# Microcontroller.net
KiCad netlist of a schematic drawn in Altium Designer
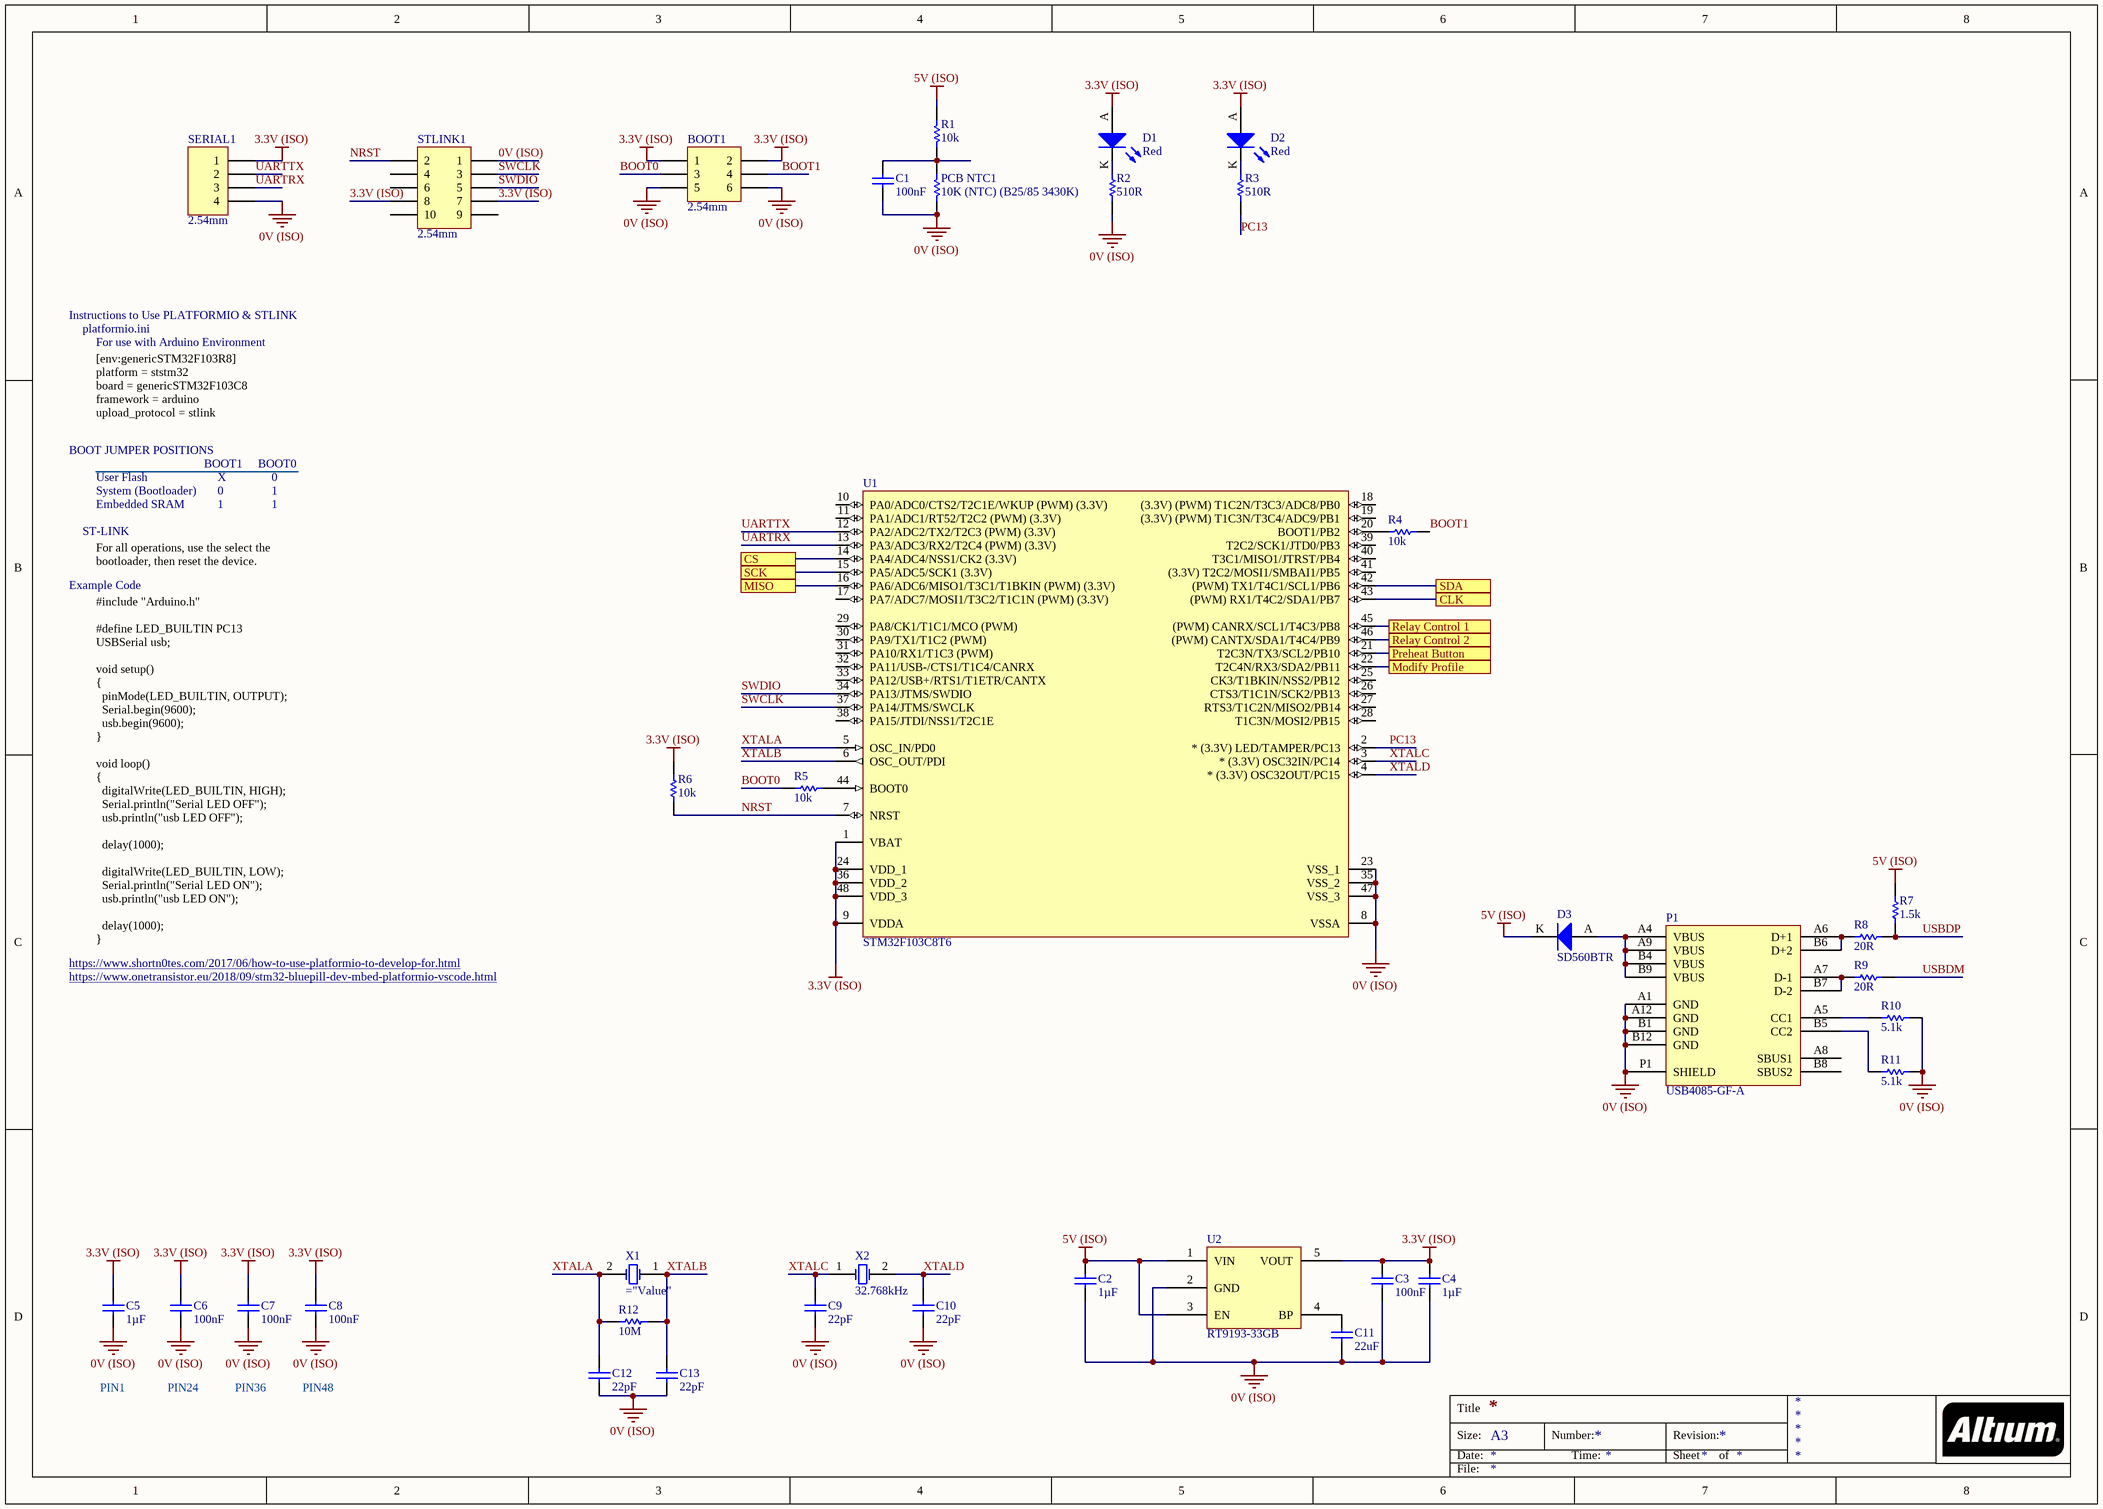
[diagram p0: Microcontroller.SchDoc]

(export (version "E")
  (design (tool "Eeschema 10.0.6"))
  (components
    (comp (ref "BOOT1")
      (value "2.54mm")
      (footprint "TH 2.54mm Header 2x3")
      (fields (field (name "PART NUMBER") "TH 2.54mm Header 2x3") (field (name "CONTACT") "NA"))
      (libsource (lib "ts_20-standard-connectors") (part "Header 2x3"))
    )
    (comp (ref "C1")
      (value "100nF")
      (footprint "0805")
      (fields
        (field (name "PART NUMBER") "GCM21BR71E104KA37L")
        (field (name "TOLERANCE") "10%")
        (field (name "MANUFACTURER") "muRata")
      )
      (libsource (lib "ts_20-standard-library") (part "Capacitor"))
    )
    (comp (ref "C2")
      (value "1µF")
      (footprint "0805")
      (fields
        (field (name "PART NUMBER") "GCM21BR71H105KA03L")
        (field (name "TOLERANCE") "±10%")
        (field (name "MANUFACTURER") "muRata")
      )
      (libsource (lib "ts_20-standard-library") (part "Capacitor"))
    )
    (comp (ref "C3")
      (value "100nF")
      (footprint "0805")
      (fields
        (field (name "PART NUMBER") "GCM21BR71H104KA37L")
        (field (name "TOLERANCE") "±10%")
        (field (name "MANUFACTURER") "muRata")
      )
      (libsource (lib "ts_20-standard-library") (part "Capacitor"))
    )
    (comp (ref "C4")
      (value "1µF")
      (footprint "0805")
      (fields
        (field (name "PART NUMBER") "GCM21BR71H105KA03L")
        (field (name "TOLERANCE") "±10%")
        (field (name "MANUFACTURER") "muRata")
      )
      (libsource (lib "ts_20-standard-library") (part "Capacitor"))
    )
    (comp (ref "C5")
      (value "1µF")
      (footprint "0805")
      (fields
        (field (name "PART NUMBER") "GCM21BR71H105KA03L")
        (field (name "TOLERANCE") "±10%")
        (field (name "MANUFACTURER") "muRata")
      )
      (libsource (lib "ts_20-standard-library") (part "Capacitor"))
    )
    (comp (ref "C6")
      (value "100nF")
      (footprint "0805")
      (fields
        (field (name "PART NUMBER") "GCM21BR71H104KA37L")
        (field (name "TOLERANCE") "±10%")
        (field (name "MANUFACTURER") "muRata")
      )
      (libsource (lib "ts_20-standard-library") (part "Capacitor"))
    )
    (comp (ref "C7")
      (value "100nF")
      (footprint "0805")
      (fields
        (field (name "PART NUMBER") "GCM21BR71H104KA37L")
        (field (name "TOLERANCE") "±10%")
        (field (name "MANUFACTURER") "muRata")
      )
      (libsource (lib "ts_20-standard-library") (part "Capacitor"))
    )
    (comp (ref "C8")
      (value "100nF")
      (footprint "0805")
      (fields
        (field (name "PART NUMBER") "GCM21BR71H104KA37L")
        (field (name "TOLERANCE") "±10%")
        (field (name "MANUFACTURER") "muRata")
      )
      (libsource (lib "ts_20-standard-library") (part "Capacitor"))
    )
    (comp (ref "C9")
      (value "22pF")
      (footprint "0805")
      (fields
        (field (name "PART NUMBER") "GRM21A5C2E220JW01D")
        (field (name "TOLERANCE") "±5%")
        (field (name "MANUFACTURER") "muRata")
      )
      (libsource (lib "ts_20-standard-library") (part "Capacitor"))
    )
    (comp (ref "C10")
      (value "22pF")
      (footprint "0805")
      (fields
        (field (name "PART NUMBER") "GRM21A5C2E220JW01D")
        (field (name "TOLERANCE") "±5%")
        (field (name "MANUFACTURER") "muRata")
      )
      (libsource (lib "ts_20-standard-library") (part "Capacitor"))
    )
    (comp (ref "C11")
      (value "22uF")
      (footprint "0805")
      (fields
        (field (name "PART NUMBER") "GRM21BR61A226ME51L")
        (field (name "TOLERANCE") "20%")
        (field (name "MANUFACTURER") "muRata")
      )
      (libsource (lib "ts_20-standard-library") (part "Capacitor"))
    )
    (comp (ref "C12")
      (value "22pF")
      (footprint "0805")
      (fields
        (field (name "PART NUMBER") "GRM21A5C2E220JW01D")
        (field (name "TOLERANCE") "±5%")
        (field (name "MANUFACTURER") "muRata")
      )
      (libsource (lib "ts_20-standard-library") (part "Capacitor"))
    )
    (comp (ref "C13")
      (value "22pF")
      (footprint "0805")
      (fields
        (field (name "PART NUMBER") "GRM21A5C2E220JW01D")
        (field (name "TOLERANCE") "±5%")
        (field (name "MANUFACTURER") "muRata")
      )
      (libsource (lib "ts_20-standard-library") (part "Capacitor"))
    )
    (comp (ref "D1")
      (value "Red")
      (footprint "0805 LED")
      (description "Red LED Indication - Discrete 1.75V 0805 (2012 Metric)")
      (fields (field (name "MANUFACTURER") "ROHM Semiconductor") (field (name "PART NUMBER") "SML-210LTT86"))
      (libsource (lib "ts_20-standard-library") (part "LED"))
    )
    (comp (ref "D2")
      (value "Red")
      (footprint "0805 LED")
      (description "Red LED Indication - Discrete 1.75V 0805 (2012 Metric)")
      (fields (field (name "MANUFACTURER") "ROHM Semiconductor") (field (name "PART NUMBER") "SML-210LTT86"))
      (libsource (lib "ts_20-standard-library") (part "LED"))
    )
    (comp (ref "D3")
      (value "SD560BTR")
      (footprint "SMB Diode")
      (description "1.2V_F 600V 5A SMB")
      (fields
        (field (name "MANUFACTURER") "SMC Diode Solutions")
        (field (name "DIGIKEY PART NUMBER") "1655-1530-2-ND")
      )
      (libsource (lib "ts_20-standard-library") (part "Diode"))
    )
    (comp (ref "P1")
      (value "USB4085-GF-A")
      (footprint "USB4085-GF-A")
      (description "USB - C (Type - C) USB 2.0 Receptacle Connector 16 Position Through Hole, Right Angle")
      (fields (field (name "DIGIKEY PART NUMBER") "2073-USB4085-GF-ACT-ND"))
      (libsource (lib "ts_20-standard-connectors") (part "USB4085-GF-A"))
    )
    (comp (ref "PCB NTC1")
      (value "10K (NTC) (B25/85 3430K)")
      (footprint "0805")
      (fields
        (field (name "PART NUMBER") "NTCS0805E3103FLT")
        (field (name "MANUFACTURER") "Vishay Beyschlag")
        (field (name "TOLERANCE") "0.01")
      )
      (libsource (lib "ts_20-standard-library") (part "Resistor"))
    )
    (comp (ref "R1")
      (value "10k")
      (footprint "0805")
      (fields
        (field (name "PART NUMBER") "RC0805FR0710KL")
        (field (name "MANUFACTURER") "YAGEO")
        (field (name "TOLERANCE") "0.01")
      )
      (libsource (lib "ts_20-standard-library") (part "Resistor"))
    )
    (comp (ref "R2")
      (value "510R")
      (footprint "0805")
      (fields
        (field (name "MANUFACTURER") "YAGEO")
        (field (name "PART NUMBER") "RC0805FR07510RL")
        (field (name "TOLERANCE") "0.01")
      )
      (libsource (lib "ts_20-standard-library") (part "Resistor"))
    )
    (comp (ref "R3")
      (value "510R")
      (footprint "0805")
      (fields
        (field (name "MANUFACTURER") "YAGEO")
        (field (name "PART NUMBER") "RC0805FR07510RL")
        (field (name "TOLERANCE") "0.01")
      )
      (libsource (lib "ts_20-standard-library") (part "Resistor"))
    )
    (comp (ref "R4")
      (value "10k")
      (footprint "0805")
      (fields
        (field (name "PART NUMBER") "RC0805FR0710KL")
        (field (name "MANUFACTURER") "YAGEO")
        (field (name "TOLERANCE") "0.01")
      )
      (libsource (lib "ts_20-standard-library") (part "Resistor"))
    )
    (comp (ref "R5")
      (value "10k")
      (footprint "0805")
      (fields
        (field (name "PART NUMBER") "RC0805FR0710KL")
        (field (name "MANUFACTURER") "YAGEO")
        (field (name "TOLERANCE") "0.01")
      )
      (libsource (lib "ts_20-standard-library") (part "Resistor"))
    )
    (comp (ref "R6")
      (value "10k")
      (footprint "0805")
      (fields
        (field (name "MANUFACTURER") "YAGEO")
        (field (name "PART NUMBER") "RC0805FR0710KL")
        (field (name "TOLERANCE") "0.01")
      )
      (libsource (lib "ts_20-standard-library") (part "Resistor"))
    )
    (comp (ref "R7")
      (value "1.5k")
      (footprint "0805")
      (fields
        (field (name "PART NUMBER") "RC0805FR071K5L")
        (field (name "MANUFACTURER") "YAGEO")
        (field (name "TOLERANCE") "0.01")
      )
      (libsource (lib "ts_20-standard-library") (part "Resistor"))
    )
    (comp (ref "R8")
      (value "20R")
      (footprint "0805")
      (fields
        (field (name "PART NUMBER") "RC0805FR0720RL")
        (field (name "MANUFACTURER") "YAGEO")
        (field (name "TOLERANCE") "0.01")
      )
      (libsource (lib "ts_20-standard-library") (part "Resistor"))
    )
    (comp (ref "R9")
      (value "20R")
      (footprint "0805")
      (fields
        (field (name "PART NUMBER") "RC0805FR0720RL")
        (field (name "MANUFACTURER") "YAGEO")
        (field (name "TOLERANCE") "0.01")
      )
      (libsource (lib "ts_20-standard-library") (part "Resistor"))
    )
    (comp (ref "R10")
      (value "5.1k")
      (footprint "0805")
      (fields
        (field (name "PART NUMBER") "RC0805FR075K1L")
        (field (name "MANUFACTURER") "YAGEO")
        (field (name "TOLERANCE") "0.01")
      )
      (libsource (lib "ts_20-standard-library") (part "Resistor"))
    )
    (comp (ref "R11")
      (value "5.1k")
      (footprint "0805")
      (fields
        (field (name "PART NUMBER") "RC0805FR075K1L")
        (field (name "MANUFACTURER") "YAGEO")
        (field (name "TOLERANCE") "0.01")
      )
      (libsource (lib "ts_20-standard-library") (part "Resistor"))
    )
    (comp (ref "R12")
      (value "10M")
      (footprint "0805")
      (fields
        (field (name "PART NUMBER") "RC0805FR0710ML")
        (field (name "MANUFACTURER") "YAGEO")
        (field (name "TOLERANCE") "0.01")
      )
      (libsource (lib "ts_20-standard-library") (part "Resistor"))
    )
    (comp (ref "SERIAL1")
      (value "2.54mm")
      (footprint "TH 2.54mm Header 1x4")
      (fields (field (name "PART NUMBER") "TH 2.54mm Header 1x4") (field (name "CONTACT") "NA"))
      (libsource (lib "ts_20-standard-connectors") (part "Header 1x4"))
    )
    (comp (ref "STLINK1")
      (value "2.54mm")
      (footprint "TH 2.54mm Header 2x5")
      (fields (field (name "PART NUMBER") "TH 2.54mm Header 2x5") (field (name "CONTACT") "NA"))
      (libsource (lib "ts_20-standard-connectors") (part "Header 2x5"))
    )
    (comp (ref "U1")
      (value "STM32F103C8T6")
      (footprint "STM 48-LQFP")
      (description "ARM® Cortex®-M3 STM32F1 Microcontroller IC 32-Bit 72MHz 64KB (64K x 8) FLASH")
      (fields
        (field (name "MANUFACTURER") "STMicroelectronics")
        (field (name "DIGIKEY PART NUMBER") "497-6063-ND")
      )
      (libsource (lib "ts_20-standard-library") (part "STM32F103C8T6"))
    )
    (comp (ref "U2")
      (value "RT9193-33GB")
      (footprint "RICHTEK SOT-23-5")
      (description "IC REG LINEAR 3.3V 300MA SOT23-5")
      (fields (field (name "MANUFACTURER") "Richtek") (field (name "DIGIKEY PART NUMBER") "1028-1014-1-ND"))
      (libsource (lib "ts_20-standard-library") (part "RT9193-33GB"))
    )
    (comp (ref "X1")
      (value "~")
      (footprint "Abracon HC-49/US")
      (fields
        (field (name "PART NUMBER") "ABLS-16.000MHZ-B4-T")
        (field (name "MANUFACTURER") "Abracon LLC")
        (field (name "DIGIKEY PART NUMBER") "535-10226-1-ND")
      )
      (libsource (lib "ts_20-standard-library") (part "Crystal"))
    )
    (comp (ref "X2")
      (value "32.768kHz")
      (footprint "EPSON 2-SMD")
      (fields
        (field (name "PART NUMBER") "FC-135 32.7680KA-A5")
        (field (name "MANUFACTURER") "EPSON")
        (field (name "DIGIKEY PART NUMBER") "SER4103TR-ND")
      )
      (libsource (lib "ts_20-standard-library") (part "Crystal"))
    )
  )
  (nets
    (net (code "1") (name "/BOOT0") (class "Default")
      (node (ref "BOOT1") (pin "3") (pinfunction "3_3") (pintype "passive"))
      (node (ref "R5") (pin "1") (pinfunction "1_1") (pintype "passive"))
    )
    (net (code "2") (name "/BOOT1") (class "Default")
      (node (ref "BOOT1") (pin "4") (pinfunction "4_4") (pintype "passive"))
      (node (ref "R4") (pin "2") (pinfunction "2_2") (pintype "passive"))
    )
    (net (code "3") (name "/CLK") (class "Default")
      (node (ref "U1") (pin "43") (pinfunction "(PWM)_RX1/T4C2/SDA1/PB7_43") (pintype "bidirectional"))
    )
    (net (code "4") (name "/CS") (class "Default")
      (node (ref "U1") (pin "14") (pinfunction "PA4/ADC4/NSS1/CK2_(3.3V)_14") (pintype "bidirectional"))
    )
    (net (code "5") (name "/MISO") (class "Default")
      (node (ref "U1") (pin "16") (pinfunction "PA6/ADC6/MISO1/T3C1/T1BKIN_(PWM)_(3.3V)_16") (pintype "bidirectional"))
    )
    (net (code "6") (name "/Modify Profile") (class "Default")
      (node (ref "U1") (pin "22") (pinfunction "T2C4N/RX3/SDA2/PB11_22") (pintype "bidirectional"))
    )
    (net (code "7") (name "/NRST") (class "Default")
      (node (ref "R6") (pin "1") (pinfunction "1_1") (pintype "passive"))
      (node (ref "STLINK1") (pin "2") (pinfunction "2_2") (pintype "passive"))
      (node (ref "U1") (pin "7") (pinfunction "NRST_7") (pintype "bidirectional"))
    )
    (net (code "8") (name "/PC13") (class "Default")
      (node (ref "R3") (pin "1") (pinfunction "1_1") (pintype "passive"))
      (node (ref "U1") (pin "2") (pinfunction "*_(3.3V)_LED/TAMPER/PC13_2") (pintype "bidirectional"))
    )
    (net (code "9") (name "/Preheat Button") (class "Default")
      (node (ref "U1") (pin "21") (pinfunction "T2C3N/TX3/SCL2/PB10_21") (pintype "bidirectional"))
    )
    (net (code "10") (name "/Relay Control 1") (class "Default")
      (node (ref "U1") (pin "45") (pinfunction "(PWM)_CANRX/SCL1/T4C3/PB8_45") (pintype "bidirectional"))
    )
    (net (code "11") (name "/Relay Control 2") (class "Default")
      (node (ref "U1") (pin "46") (pinfunction "(PWM)_CANTX/SDA1/T4C4/PB9_46") (pintype "bidirectional"))
    )
    (net (code "12") (name "/SCK") (class "Default")
      (node (ref "U1") (pin "15") (pinfunction "PA5/ADC5/SCK1_(3.3V)_15") (pintype "bidirectional"))
    )
    (net (code "13") (name "/SDA") (class "Default")
      (node (ref "U1") (pin "42") (pinfunction "(PWM)_TX1/T4C1/SCL1/PB6_42") (pintype "bidirectional"))
    )
    (net (code "14") (name "/SWCLK") (class "Default")
      (node (ref "STLINK1") (pin "3") (pinfunction "3_3") (pintype "passive"))
      (node (ref "U1") (pin "37") (pinfunction "PA14/JTMS/SWCLK_37") (pintype "bidirectional"))
    )
    (net (code "15") (name "/SWDIO") (class "Default")
      (node (ref "STLINK1") (pin "5") (pinfunction "5_5") (pintype "passive"))
      (node (ref "U1") (pin "34") (pinfunction "PA13/JTMS/SWDIO_34") (pintype "bidirectional"))
    )
    (net (code "16") (name "/UARTRX") (class "Default")
      (node (ref "SERIAL1") (pin "3") (pinfunction "3_3") (pintype "passive"))
      (node (ref "U1") (pin "13") (pinfunction "PA3/ADC3/RX2/T2C4_(PWM)_(3.3V)_13") (pintype "bidirectional"))
    )
    (net (code "17") (name "/UARTTX") (class "Default")
      (node (ref "SERIAL1") (pin "2") (pinfunction "2_2") (pintype "passive"))
      (node (ref "U1") (pin "12") (pinfunction "PA2/ADC2/TX2/T2C3_(PWM)_(3.3V)_12") (pintype "bidirectional"))
    )
    (net (code "18") (name "/USBDM") (class "Default")
      (node (ref "R9") (pin "2") (pinfunction "2_2") (pintype "passive"))
    )
    (net (code "19") (name "/USBDP") (class "Default")
      (node (ref "R7") (pin "1") (pinfunction "1_1") (pintype "passive"))
      (node (ref "R8") (pin "2") (pinfunction "2_2") (pintype "passive"))
    )
    (net (code "20") (name "/XTALA") (class "Default")
      (node (ref "C12") (pin "2") (pinfunction "2_2") (pintype "passive"))
      (node (ref "R12") (pin "2") (pinfunction "2_2") (pintype "passive"))
      (node (ref "U1") (pin "5") (pinfunction "OSC_IN/PD0_5") (pintype "input"))
      (node (ref "X1") (pin "2") (pinfunction "OSC2_2") (pintype "passive"))
    )
    (net (code "21") (name "/XTALB") (class "Default")
      (node (ref "C13") (pin "2") (pinfunction "2_2") (pintype "passive"))
      (node (ref "R12") (pin "1") (pinfunction "1_1") (pintype "passive"))
      (node (ref "U1") (pin "6") (pinfunction "OSC_OUT/PDI_6") (pintype "output"))
      (node (ref "X1") (pin "1") (pinfunction "OSC1_1") (pintype "passive"))
    )
    (net (code "22") (name "/XTALC") (class "Default")
      (node (ref "C9") (pin "2") (pinfunction "2_2") (pintype "passive"))
      (node (ref "U1") (pin "3") (pinfunction "*_(3.3V)_OSC32IN/PC14_3") (pintype "bidirectional"))
      (node (ref "X2") (pin "1") (pinfunction "OSC1_1") (pintype "passive"))
    )
    (net (code "23") (name "/XTALD") (class "Default")
      (node (ref "C10") (pin "2") (pinfunction "2_2") (pintype "passive"))
      (node (ref "U1") (pin "4") (pinfunction "*_(3.3V)_OSC32OUT/PC15_4") (pintype "bidirectional"))
      (node (ref "X2") (pin "2") (pinfunction "OSC2_2") (pintype "passive"))
    )
    (net (code "24") (name "0V (ISO)") (class "Default")
      (node (ref "BOOT1") (pin "5") (pinfunction "5_5") (pintype "passive"))
      (node (ref "BOOT1") (pin "6") (pinfunction "6_6") (pintype "passive"))
      (node (ref "C1") (pin "1") (pinfunction "1_1") (pintype "passive"))
      (node (ref "C10") (pin "1") (pinfunction "1_1") (pintype "passive"))
      (node (ref "C11") (pin "1") (pinfunction "1_1") (pintype "passive"))
      (node (ref "C12") (pin "1") (pinfunction "1_1") (pintype "passive"))
      (node (ref "C13") (pin "1") (pinfunction "1_1") (pintype "passive"))
      (node (ref "C2") (pin "1") (pinfunction "1_1") (pintype "passive"))
      (node (ref "C3") (pin "1") (pinfunction "1_1") (pintype "passive"))
      (node (ref "C4") (pin "1") (pinfunction "1_1") (pintype "passive"))
      (node (ref "C5") (pin "1") (pinfunction "1_1") (pintype "passive"))
      (node (ref "C6") (pin "1") (pinfunction "1_1") (pintype "passive"))
      (node (ref "C7") (pin "1") (pinfunction "1_1") (pintype "passive"))
      (node (ref "C8") (pin "1") (pinfunction "1_1") (pintype "passive"))
      (node (ref "C9") (pin "1") (pinfunction "1_1") (pintype "passive"))
      (node (ref "P1") (pin "A1") (pinfunction "GND_A1") (pintype "passive"))
      (node (ref "P1") (pin "A12") (pinfunction "GND_A12") (pintype "passive"))
      (node (ref "P1") (pin "B1") (pinfunction "GND_B1") (pintype "passive"))
      (node (ref "P1") (pin "B12") (pinfunction "GND_B12") (pintype "passive"))
      (node (ref "P1") (pin "P1") (pinfunction "SHIELD_P1") (pintype "passive"))
      (node (ref "PCB NTC1") (pin "1") (pinfunction "1_1") (pintype "passive"))
      (node (ref "R10") (pin "2") (pinfunction "2_2") (pintype "passive"))
      (node (ref "R11") (pin "2") (pinfunction "2_2") (pintype "passive"))
      (node (ref "R2") (pin "1") (pinfunction "1_1") (pintype "passive"))
      (node (ref "SERIAL1") (pin "4") (pinfunction "4_4") (pintype "passive"))
      (node (ref "STLINK1") (pin "1") (pinfunction "1_1") (pintype "passive"))
      (node (ref "U1") (pin "23") (pinfunction "VSS_1_23") (pintype "power_in"))
      (node (ref "U1") (pin "35") (pinfunction "VSS_2_35") (pintype "power_in"))
      (node (ref "U1") (pin "47") (pinfunction "VSS_3_47") (pintype "power_in"))
      (node (ref "U1") (pin "8") (pinfunction "VSSA_8") (pintype "power_in"))
      (node (ref "U2") (pin "2") (pinfunction "GND_2") (pintype "passive"))
    )
    (net (code "25") (name "3.3V (ISO)") (class "Default")
      (node (ref "BOOT1") (pin "1") (pinfunction "1_1") (pintype "passive"))
      (node (ref "BOOT1") (pin "2") (pinfunction "2_2") (pintype "passive"))
      (node (ref "C3") (pin "2") (pinfunction "2_2") (pintype "passive"))
      (node (ref "C4") (pin "2") (pinfunction "2_2") (pintype "passive"))
      (node (ref "C5") (pin "2") (pinfunction "2_2") (pintype "passive"))
      (node (ref "C6") (pin "2") (pinfunction "2_2") (pintype "passive"))
      (node (ref "C7") (pin "2") (pinfunction "2_2") (pintype "passive"))
      (node (ref "C8") (pin "2") (pinfunction "2_2") (pintype "passive"))
      (node (ref "D1") (pin "A") (pinfunction "A_A") (pintype "passive"))
      (node (ref "D2") (pin "A") (pinfunction "A_A") (pintype "passive"))
      (node (ref "R6") (pin "2") (pinfunction "2_2") (pintype "passive"))
      (node (ref "SERIAL1") (pin "1") (pinfunction "1_1") (pintype "passive"))
      (node (ref "STLINK1") (pin "7") (pinfunction "7_7") (pintype "passive"))
      (node (ref "STLINK1") (pin "8") (pinfunction "8_8") (pintype "passive"))
      (node (ref "U1") (pin "1") (pinfunction "VBAT_1") (pintype "power_in"))
      (node (ref "U1") (pin "24") (pinfunction "VDD_1_24") (pintype "power_in"))
      (node (ref "U1") (pin "36") (pinfunction "VDD_2_36") (pintype "power_in"))
      (node (ref "U1") (pin "48") (pinfunction "VDD_3_48") (pintype "power_in"))
      (node (ref "U1") (pin "9") (pinfunction "VDDA_9") (pintype "power_in"))
      (node (ref "U2") (pin "5") (pinfunction "VOUT_5") (pintype "passive"))
    )
    (net (code "26") (name "5V (ISO)") (class "Default")
      (node (ref "C2") (pin "2") (pinfunction "2_2") (pintype "passive"))
      (node (ref "D3") (pin "K") (pinfunction "K_K") (pintype "passive"))
      (node (ref "R1") (pin "2") (pinfunction "2_2") (pintype "passive"))
      (node (ref "R7") (pin "2") (pinfunction "2_2") (pintype "passive"))
      (node (ref "U2") (pin "1") (pinfunction "VIN_1") (pintype "passive"))
      (node (ref "U2") (pin "3") (pinfunction "EN_3") (pintype "passive"))
    )
    (net (code "27") (name "Net-(C1-Pad2)") (class "Default")
      (node (ref "C1") (pin "2") (pinfunction "2_2") (pintype "passive"))
      (node (ref "PCB NTC1") (pin "2") (pinfunction "2_2") (pintype "passive"))
      (node (ref "R1") (pin "1") (pinfunction "1_1") (pintype "passive"))
    )
    (net (code "28") (name "Net-(D1-PadK)") (class "Default")
      (node (ref "D1") (pin "K") (pinfunction "K_K") (pintype "passive"))
      (node (ref "R2") (pin "2") (pinfunction "2_2") (pintype "passive"))
    )
    (net (code "29") (name "Net-(D2-PadK)") (class "Default")
      (node (ref "D2") (pin "K") (pinfunction "K_K") (pintype "passive"))
      (node (ref "R3") (pin "2") (pinfunction "2_2") (pintype "passive"))
    )
    (net (code "30") (name "Net-(D3-PadA)") (class "Default")
      (node (ref "D3") (pin "A") (pinfunction "A_A") (pintype "passive"))
      (node (ref "P1") (pin "A4") (pinfunction "VBUS_A4") (pintype "passive"))
      (node (ref "P1") (pin "A9") (pinfunction "VBUS_A9") (pintype "passive"))
      (node (ref "P1") (pin "B4") (pinfunction "VBUS_B4") (pintype "passive"))
      (node (ref "P1") (pin "B9") (pinfunction "VBUS_B9") (pintype "passive"))
    )
    (net (code "31") (name "Net-(P1-CC1)") (class "Default")
      (node (ref "P1") (pin "A5") (pinfunction "CC1_A5") (pintype "passive"))
      (node (ref "R10") (pin "1") (pinfunction "1_1") (pintype "passive"))
    )
    (net (code "32") (name "Net-(P1-CC2)") (class "Default")
      (node (ref "P1") (pin "B5") (pinfunction "CC2_B5") (pintype "passive"))
      (node (ref "R11") (pin "1") (pinfunction "1_1") (pintype "passive"))
    )
    (net (code "33") (name "Net-(P1-D+1)") (class "Default")
      (node (ref "P1") (pin "A6") (pinfunction "D+1_A6") (pintype "passive"))
      (node (ref "P1") (pin "B6") (pinfunction "D+2_B6") (pintype "passive"))
      (node (ref "R8") (pin "1") (pinfunction "1_1") (pintype "passive"))
    )
    (net (code "34") (name "Net-(P1-D-1)") (class "Default")
      (node (ref "P1") (pin "A7") (pinfunction "D-1_A7") (pintype "passive"))
      (node (ref "P1") (pin "B7") (pinfunction "D-2_B7") (pintype "passive"))
      (node (ref "R9") (pin "1") (pinfunction "1_1") (pintype "passive"))
    )
    (net (code "35") (name "Net-(U1-BOOT0)") (class "Default")
      (node (ref "R5") (pin "2") (pinfunction "2_2") (pintype "passive"))
      (node (ref "U1") (pin "44") (pinfunction "BOOT0_44") (pintype "input"))
    )
    (net (code "36") (name "Net-(U1-BOOT1{slash}PB2)") (class "Default")
      (node (ref "R4") (pin "1") (pinfunction "1_1") (pintype "passive"))
      (node (ref "U1") (pin "20") (pinfunction "BOOT1/PB2_20") (pintype "bidirectional"))
    )
    (net (code "37") (name "Net-(U2-BP)") (class "Default")
      (node (ref "C11") (pin "2") (pinfunction "2_2") (pintype "passive"))
      (node (ref "U2") (pin "4") (pinfunction "BP_4") (pintype "passive"))
    )
    (net (code "38") (name "unconnected-(P1-SBUS1-PadA8)") (class "Default")
      (node (ref "P1") (pin "A8") (pinfunction "SBUS1_A8") (pintype "passive"))
    )
    (net (code "39") (name "unconnected-(P1-SBUS2-PadB8)") (class "Default")
      (node (ref "P1") (pin "B8") (pinfunction "SBUS2_B8") (pintype "passive"))
    )
    (net (code "40") (name "unconnected-(STLINK1-Pad4)") (class "Default")
      (node (ref "STLINK1") (pin "4") (pinfunction "4_4") (pintype "passive"))
    )
    (net (code "41") (name "unconnected-(STLINK1-Pad6)") (class "Default")
      (node (ref "STLINK1") (pin "6") (pinfunction "6_6") (pintype "passive"))
    )
    (net (code "42") (name "unconnected-(STLINK1-Pad9)") (class "Default")
      (node (ref "STLINK1") (pin "9") (pinfunction "9_9") (pintype "passive"))
    )
    (net (code "43") (name "unconnected-(STLINK1-Pad10)") (class "Default")
      (node (ref "STLINK1") (pin "10") (pinfunction "10_10") (pintype "passive"))
    )
    (net (code "44") (name "unconnected-(U1-(3.3V)_(PWM)_T1C2N{slash}T3C3{slash}ADC8{slash}PB0-Pad18)") (class "Default")
      (node (ref "U1") (pin "18") (pinfunction "(3.3V)_(PWM)_T1C2N/T3C3/ADC8/PB0_18") (pintype "bidirectional"))
    )
    (net (code "45") (name "unconnected-(U1-(3.3V)_(PWM)_T1C3N{slash}T3C4{slash}ADC9{slash}PB1-Pad19)") (class "Default")
      (node (ref "U1") (pin "19") (pinfunction "(3.3V)_(PWM)_T1C3N/T3C4/ADC9/PB1_19") (pintype "bidirectional"))
    )
    (net (code "46") (name "unconnected-(U1-(3.3V)_T2C2{slash}MOSI1{slash}SMBAI1{slash}PB5-Pad41)") (class "Default")
      (node (ref "U1") (pin "41") (pinfunction "(3.3V)_T2C2/MOSI1/SMBAI1/PB5_41") (pintype "bidirectional"))
    )
    (net (code "47") (name "unconnected-(U1-CK3{slash}T1BKIN{slash}NSS2{slash}PB12-Pad25)") (class "Default")
      (node (ref "U1") (pin "25") (pinfunction "CK3/T1BKIN/NSS2/PB12_25") (pintype "bidirectional"))
    )
    (net (code "48") (name "unconnected-(U1-CTS3{slash}T1C1N{slash}SCK2{slash}PB13-Pad26)") (class "Default")
      (node (ref "U1") (pin "26") (pinfunction "CTS3/T1C1N/SCK2/PB13_26") (pintype "bidirectional"))
    )
    (net (code "49") (name "unconnected-(U1-PA0{slash}ADC0{slash}CTS2{slash}T2C1E{slash}WKUP_(PWM)_(3.3V)-Pad10)") (class "Default")
      (node (ref "U1") (pin "10") (pinfunction "PA0/ADC0/CTS2/T2C1E/WKUP_(PWM)_(3.3V)_10") (pintype "bidirectional"))
    )
    (net (code "50") (name "unconnected-(U1-PA1{slash}ADC1{slash}RT52{slash}T2C2_(PWM)_(3.3V)-Pad11)") (class "Default")
      (node (ref "U1") (pin "11") (pinfunction "PA1/ADC1/RT52/T2C2_(PWM)_(3.3V)_11") (pintype "bidirectional"))
    )
    (net (code "51") (name "unconnected-(U1-PA7{slash}ADC7{slash}MOSI1{slash}T3C2{slash}T1C1N_(PWM)_(3.3V)-Pad17)") (class "Default")
      (node (ref "U1") (pin "17") (pinfunction "PA7/ADC7/MOSI1/T3C2/T1C1N_(PWM)_(3.3V)_17") (pintype "bidirectional"))
    )
    (net (code "52") (name "unconnected-(U1-PA8{slash}CK1{slash}T1C1{slash}MCO_(PWM)-Pad29)") (class "Default")
      (node (ref "U1") (pin "29") (pinfunction "PA8/CK1/T1C1/MCO_(PWM)_29") (pintype "bidirectional"))
    )
    (net (code "53") (name "unconnected-(U1-PA9{slash}TX1{slash}T1C2_(PWM)-Pad30)") (class "Default")
      (node (ref "U1") (pin "30") (pinfunction "PA9/TX1/T1C2_(PWM)_30") (pintype "bidirectional"))
    )
    (net (code "54") (name "unconnected-(U1-PA10{slash}RX1{slash}T1C3_(PWM)-Pad31)") (class "Default")
      (node (ref "U1") (pin "31") (pinfunction "PA10/RX1/T1C3_(PWM)_31") (pintype "bidirectional"))
    )
    (net (code "55") (name "unconnected-(U1-PA11{slash}USB-{slash}CTS1{slash}T1C4{slash}CANRX-Pad32)") (class "Default")
      (node (ref "U1") (pin "32") (pinfunction "PA11/USB-/CTS1/T1C4/CANRX_32") (pintype "bidirectional"))
    )
    (net (code "56") (name "unconnected-(U1-PA12{slash}USB+{slash}RTS1{slash}T1ETR{slash}CANTX-Pad33)") (class "Default")
      (node (ref "U1") (pin "33") (pinfunction "PA12/USB+/RTS1/T1ETR/CANTX_33") (pintype "bidirectional"))
    )
    (net (code "57") (name "unconnected-(U1-PA15{slash}JTDI{slash}NSS1{slash}T2C1E-Pad38)") (class "Default")
      (node (ref "U1") (pin "38") (pinfunction "PA15/JTDI/NSS1/T2C1E_38") (pintype "bidirectional"))
    )
    (net (code "58") (name "unconnected-(U1-RTS3{slash}T1C2N{slash}MISO2{slash}PB14-Pad27)") (class "Default")
      (node (ref "U1") (pin "27") (pinfunction "RTS3/T1C2N/MISO2/PB14_27") (pintype "bidirectional"))
    )
    (net (code "59") (name "unconnected-(U1-T1C3N{slash}MOSI2{slash}PB15-Pad28)") (class "Default")
      (node (ref "U1") (pin "28") (pinfunction "T1C3N/MOSI2/PB15_28") (pintype "bidirectional"))
    )
    (net (code "60") (name "unconnected-(U1-T2C2{slash}SCK1{slash}JTD0{slash}PB3-Pad39)") (class "Default")
      (node (ref "U1") (pin "39") (pinfunction "T2C2/SCK1/JTD0/PB3_39") (pintype "bidirectional"))
    )
    (net (code "61") (name "unconnected-(U1-T3C1{slash}MISO1{slash}JTRST{slash}PB4-Pad40)") (class "Default")
      (node (ref "U1") (pin "40") (pinfunction "T3C1/MISO1/JTRST/PB4_40") (pintype "bidirectional"))
    )
  )
)
